# BIOGAS.net
KiCad netlist of a schematic drawn in EAGLE
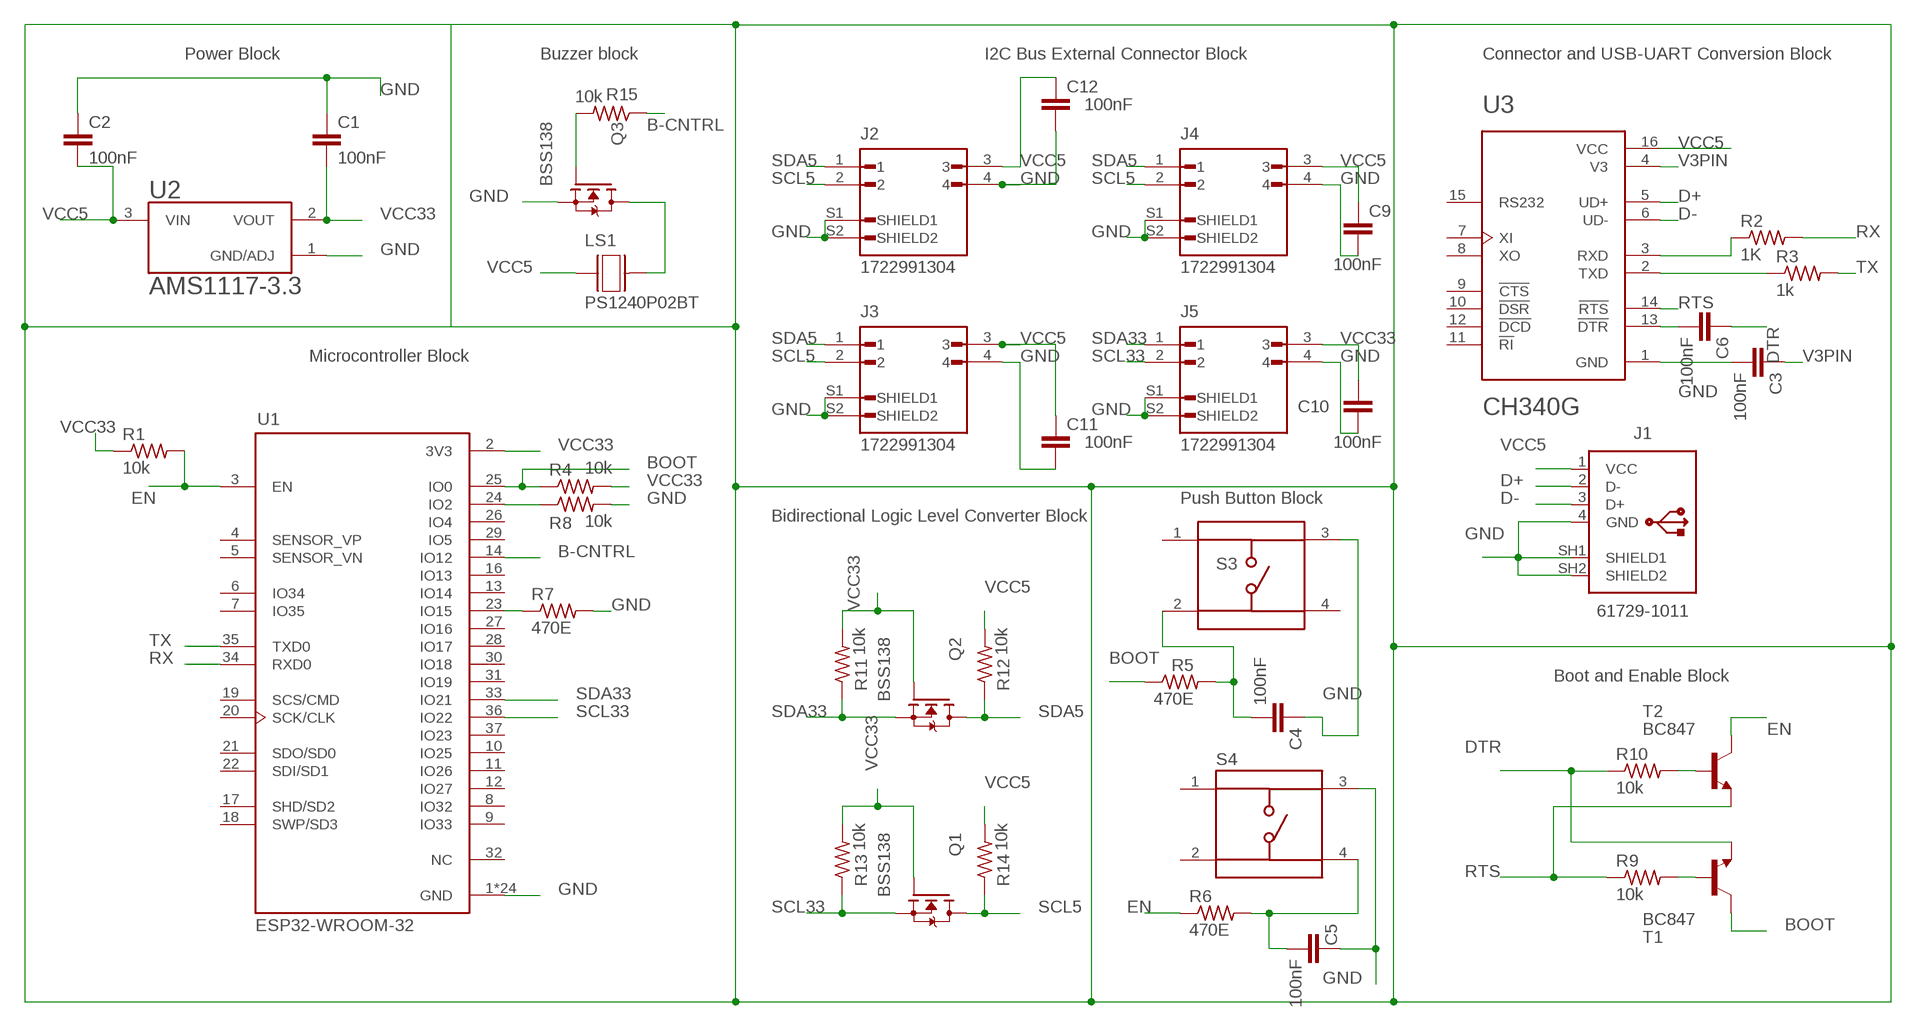
[diagram p0: schematic, sheet 1]

(export (version "E")
  (design (tool "Eeschema 10.0.6"))
  (components
    (comp (ref "C1")
      (value "100nF")
      (footprint "eagle-import:C1206")
      (libsource (lib "eagle-import") (part "CAPACITOR_SMD_1206"))
    )
    (comp (ref "C2")
      (value "100nF")
      (footprint "eagle-import:C1206")
      (libsource (lib "eagle-import") (part "CAPACITOR_SMD_1206"))
    )
    (comp (ref "C3")
      (value "100nF")
      (footprint "eagle-import:C1206")
      (libsource (lib "eagle-import") (part "CAPACITOR_SMD_1206"))
    )
    (comp (ref "C4")
      (value "100nF")
      (footprint "eagle-import:C1206")
      (libsource (lib "eagle-import") (part "CAPACITOR_SMD_1206"))
    )
    (comp (ref "C5")
      (value "100nF")
      (footprint "eagle-import:C1206")
      (libsource (lib "eagle-import") (part "CAPACITOR_SMD_1206"))
    )
    (comp (ref "C6")
      (value "100nF")
      (footprint "eagle-import:C1206")
      (libsource (lib "eagle-import") (part "CAPACITOR_SMD_1206"))
    )
    (comp (ref "C9")
      (value "100nF")
      (footprint "eagle-import:C1206")
      (libsource (lib "eagle-import") (part "CAPACITOR_SMD_1206"))
    )
    (comp (ref "C10")
      (value "100nF")
      (footprint "eagle-import:C1206")
      (libsource (lib "eagle-import") (part "CAPACITOR_SMD_1206"))
    )
    (comp (ref "C11")
      (value "100nF")
      (footprint "eagle-import:C1206")
      (libsource (lib "eagle-import") (part "CAPACITOR_SMD_1206"))
    )
    (comp (ref "C12")
      (value "100nF")
      (footprint "eagle-import:C1206")
      (libsource (lib "eagle-import") (part "CAPACITOR_SMD_1206"))
    )
    (comp (ref "J1")
      (value "61729-1011")
      (footprint "eagle-import:61729-1011BLF")
      (fields (field (name "MANUFACTURER") "Amphenol ICC (FCI)") (field (name "MPN") "61729-1011BLF"))
      (libsource (lib "eagle-import") (part "61729-1011"))
    )
    (comp (ref "J2")
      (value "1722991304")
      (footprint "eagle-import:MOLEX_1722991304")
      (fields (field (name "MANUFACTURER") "Molex"))
      (libsource (lib "eagle-import") (part "1722991304"))
    )
    (comp (ref "J3")
      (value "1722991304")
      (footprint "eagle-import:MOLEX_1722991304")
      (fields (field (name "MANUFACTURER") "Molex"))
      (libsource (lib "eagle-import") (part "1722991304"))
    )
    (comp (ref "J4")
      (value "1722991304")
      (footprint "eagle-import:MOLEX_1722991304")
      (fields (field (name "MANUFACTURER") "Molex"))
      (libsource (lib "eagle-import") (part "1722991304"))
    )
    (comp (ref "J5")
      (value "1722991304")
      (footprint "eagle-import:MOLEX_1722991304")
      (fields (field (name "MANUFACTURER") "Molex"))
      (libsource (lib "eagle-import") (part "1722991304"))
    )
    (comp (ref "LS1")
      (value "PS1240P02BT")
      (footprint "eagle-import:XDCR_PS1240P02BT")
      (fields (field (name "MF") "TDK") (field (name "MP") "PS1240P02CT3"))
      (libsource (lib "eagle-import") (part "PS1240P02BT"))
    )
    (comp (ref "Q1")
      (value "BSS138")
      (footprint "eagle-import:SOT95P240X111-3N")
      (fields (field (name "MANUFACTURER") "ON Semiconductor"))
      (libsource (lib "eagle-import") (part "BSS138"))
    )
    (comp (ref "Q2")
      (value "BSS138")
      (footprint "eagle-import:SOT95P240X111-3N")
      (fields (field (name "MANUFACTURER") "ON Semiconductor"))
      (libsource (lib "eagle-import") (part "BSS138"))
    )
    (comp (ref "Q3")
      (value "BSS138")
      (footprint "eagle-import:SOT95P240X111-3N")
      (fields (field (name "MANUFACTURER") "ON Semiconductor"))
      (libsource (lib "eagle-import") (part "BSS138"))
    )
    (comp (ref "R1")
      (value "10k")
      (footprint "eagle-import:M1206")
      (libsource (lib "eagle-import") (part "RESISTOR_SMD_1206"))
    )
    (comp (ref "R2")
      (value "1K")
      (footprint "eagle-import:M1206")
      (libsource (lib "eagle-import") (part "RESISTOR_SMD_1206"))
    )
    (comp (ref "R3")
      (value "1k")
      (footprint "eagle-import:M1206")
      (libsource (lib "eagle-import") (part "RESISTOR_SMD_1206"))
    )
    (comp (ref "R4")
      (value "10k")
      (footprint "eagle-import:M1206")
      (libsource (lib "eagle-import") (part "RESISTOR_SMD_1206"))
    )
    (comp (ref "R5")
      (value "470E")
      (footprint "eagle-import:M1206")
      (libsource (lib "eagle-import") (part "RESISTOR_SMD_1206"))
    )
    (comp (ref "R6")
      (value "470E")
      (footprint "eagle-import:M1206")
      (libsource (lib "eagle-import") (part "RESISTOR_SMD_1206"))
    )
    (comp (ref "R7")
      (value "470E")
      (footprint "eagle-import:M1206")
      (libsource (lib "eagle-import") (part "RESISTOR_SMD_1206"))
    )
    (comp (ref "R8")
      (value "10k")
      (footprint "eagle-import:M1206")
      (libsource (lib "eagle-import") (part "RESISTOR_SMD_1206"))
    )
    (comp (ref "R9")
      (value "10k")
      (footprint "eagle-import:M1206")
      (libsource (lib "eagle-import") (part "RESISTOR_SMD_1206"))
    )
    (comp (ref "R10")
      (value "10k")
      (footprint "eagle-import:M1206")
      (libsource (lib "eagle-import") (part "RESISTOR_SMD_1206"))
    )
    (comp (ref "R11")
      (value "10k")
      (footprint "eagle-import:M1206")
      (libsource (lib "eagle-import") (part "RESISTOR_SMD_1206"))
    )
    (comp (ref "R12")
      (value "10k")
      (footprint "eagle-import:M1206")
      (libsource (lib "eagle-import") (part "RESISTOR_SMD_1206"))
    )
    (comp (ref "R13")
      (value "10k")
      (footprint "eagle-import:M1206")
      (libsource (lib "eagle-import") (part "RESISTOR_SMD_1206"))
    )
    (comp (ref "R14")
      (value "10k")
      (footprint "eagle-import:M1206")
      (libsource (lib "eagle-import") (part "RESISTOR_SMD_1206"))
    )
    (comp (ref "R15")
      (value "10k")
      (footprint "eagle-import:M1206")
      (libsource (lib "eagle-import") (part "RESISTOR_SMD_1206"))
    )
    (comp (ref "S3")
      (value "TS04-66-55-BK-260-SMT")
      (footprint "eagle-import:SW_TS04-66-55-BK-260-SMT")
      (fields (field (name "MANUFACTURER") "CUI Devices"))
      (libsource (lib "eagle-import") (part "TS04-66-55-BK-260-SMT"))
    )
    (comp (ref "S4")
      (value "TS04-66-55-BK-260-SMT")
      (footprint "eagle-import:SW_TS04-66-55-BK-260-SMT")
      (fields (field (name "MANUFACTURER") "CUI Devices"))
      (libsource (lib "eagle-import") (part "TS04-66-55-BK-260-SMT"))
    )
    (comp (ref "T1")
      (value "BC847")
      (footprint "eagle-import:SOT23")
      (libsource (lib "eagle-import") (part "BC847"))
    )
    (comp (ref "T2")
      (value "BC847")
      (footprint "eagle-import:SOT23")
      (libsource (lib "eagle-import") (part "BC847"))
    )
    (comp (ref "U1")
      (value "ESP32-WROOM-32")
      (footprint "eagle-import:MODULE_ESP32-WROOM-32")
      (fields (field (name "MANUFACTURER") "Espressif Systems"))
      (libsource (lib "eagle-import") (part "ESP32-WROOM-32"))
    )
    (comp (ref "U2")
      (value "AMS1117-3.3")
      (footprint "eagle-import:SOT229P700X180-4N")
      (fields (field (name "MANUFACTURER") "Advanced Monolithic Systems"))
      (libsource (lib "eagle-import") (part "AMS1117-3.3"))
    )
    (comp (ref "U3")
      (value "CH340G")
      (footprint "eagle-import:SOIC127P600X180-16N")
      (fields (field (name "MANUFACTURER") "WCH"))
      (libsource (lib "eagle-import") (part "CH340G"))
    )
  )
  (nets
    (net (code "1") (name "/B-CNTRL") (class "Default")
      (node (ref "R15") (pin "1") (pinfunction "1_1") (pintype "passive"))
      (node (ref "U1") (pin "14") (pinfunction "IO12_14") (pintype "bidirectional"))
    )
    (net (code "2") (name "/BOOT") (class "Default")
      (node (ref "R4") (pin "1") (pinfunction "1_1") (pintype "passive"))
      (node (ref "R5") (pin "1") (pinfunction "1_1") (pintype "passive"))
      (node (ref "T1") (pin "3") (pinfunction "C_3") (pintype "passive"))
      (node (ref "U1") (pin "25") (pinfunction "IO0_25") (pintype "bidirectional"))
    )
    (net (code "3") (name "/D+") (class "Default")
      (node (ref "J1") (pin "2") (pinfunction "D-_2") (pintype "bidirectional"))
      (node (ref "U3") (pin "5") (pinfunction "UD+_5") (pintype "bidirectional"))
    )
    (net (code "4") (name "/D-") (class "Default")
      (node (ref "J1") (pin "3") (pinfunction "D+_3") (pintype "bidirectional"))
      (node (ref "U3") (pin "6") (pinfunction "UD-_6") (pintype "bidirectional"))
    )
    (net (code "5") (name "/DTR") (class "Default")
      (node (ref "C6") (pin "1") (pinfunction "1_1") (pintype "passive"))
      (node (ref "R10") (pin "1") (pinfunction "1_1") (pintype "passive"))
      (node (ref "T1") (pin "2") (pinfunction "E_2") (pintype "passive"))
    )
    (net (code "6") (name "/EN") (class "Default")
      (node (ref "R1") (pin "2") (pinfunction "2_2") (pintype "passive"))
      (node (ref "R6") (pin "1") (pinfunction "1_1") (pintype "passive"))
      (node (ref "T2") (pin "3") (pinfunction "C_3") (pintype "passive"))
      (node (ref "U1") (pin "3") (pinfunction "EN_3") (pintype "input"))
    )
    (net (code "7") (name "/GND") (class "Default")
      (node (ref "C1") (pin "1") (pinfunction "1_1") (pintype "passive"))
      (node (ref "C10") (pin "2") (pinfunction "2_2") (pintype "passive"))
      (node (ref "C11") (pin "2") (pinfunction "2_2") (pintype "passive"))
      (node (ref "C12") (pin "2") (pinfunction "2_2") (pintype "passive"))
      (node (ref "C2") (pin "1") (pinfunction "1_1") (pintype "passive"))
      (node (ref "C3") (pin "2") (pinfunction "2_2") (pintype "passive"))
      (node (ref "C4") (pin "1") (pinfunction "1_1") (pintype "passive"))
      (node (ref "C5") (pin "1") (pinfunction "1_1") (pintype "passive"))
      (node (ref "C9") (pin "2") (pinfunction "2_2") (pintype "passive"))
      (node (ref "J1") (pin "4") (pinfunction "GND_4") (pintype "power_in"))
      (node (ref "J1") (pin "SH1") (pinfunction "SHIELD1_SH1") (pintype "power_in"))
      (node (ref "J1") (pin "SH2") (pinfunction "SHIELD2_SH2") (pintype "power_in"))
      (node (ref "J2") (pin "4") (pinfunction "4_4") (pintype "passive"))
      (node (ref "J2") (pin "S1") (pinfunction "SHIELD1_S1") (pintype "passive"))
      (node (ref "J2") (pin "S2") (pinfunction "SHIELD2_S2") (pintype "passive"))
      (node (ref "J3") (pin "4") (pinfunction "4_4") (pintype "passive"))
      (node (ref "J3") (pin "S1") (pinfunction "SHIELD1_S1") (pintype "passive"))
      (node (ref "J3") (pin "S2") (pinfunction "SHIELD2_S2") (pintype "passive"))
      (node (ref "J4") (pin "4") (pinfunction "4_4") (pintype "passive"))
      (node (ref "J4") (pin "S1") (pinfunction "SHIELD1_S1") (pintype "passive"))
      (node (ref "J4") (pin "S2") (pinfunction "SHIELD2_S2") (pintype "passive"))
      (node (ref "J5") (pin "4") (pinfunction "4_4") (pintype "passive"))
      (node (ref "J5") (pin "S1") (pinfunction "SHIELD1_S1") (pintype "passive"))
      (node (ref "J5") (pin "S2") (pinfunction "SHIELD2_S2") (pintype "passive"))
      (node (ref "Q3") (pin "2") (pinfunction "S_2") (pintype "passive"))
      (node (ref "R7") (pin "2") (pinfunction "2_2") (pintype "passive"))
      (node (ref "R8") (pin "2") (pinfunction "2_2") (pintype "passive"))
      (node (ref "S3") (pin "3") (pinfunction "3_3") (pintype "passive"))
      (node (ref "S4") (pin "3") (pinfunction "3_3") (pintype "passive"))
      (node (ref "U1") (pin "1") (pinfunction "GND_1") (pintype "power_in"))
      (node (ref "U1") (pin "15") (pinfunction "GND_15") (pintype "power_in"))
      (node (ref "U1") (pin "38") (pinfunction "GND_38") (pintype "power_in"))
      (node (ref "U1") (pin "39_1") (pinfunction "GND_39_1") (pintype "power_in"))
      (node (ref "U1") (pin "39_10") (pinfunction "GND_39_10") (pintype "power_in"))
      (node (ref "U1") (pin "39_11") (pinfunction "GND_39_11") (pintype "power_in"))
      (node (ref "U1") (pin "39_12") (pinfunction "GND_39_12") (pintype "power_in"))
      (node (ref "U1") (pin "39_13") (pinfunction "GND_39_13") (pintype "power_in"))
      (node (ref "U1") (pin "39_14") (pinfunction "GND_39_14") (pintype "power_in"))
      (node (ref "U1") (pin "39_15") (pinfunction "GND_39_15") (pintype "power_in"))
      (node (ref "U1") (pin "39_16") (pinfunction "GND_39_16") (pintype "power_in"))
      (node (ref "U1") (pin "39_17") (pinfunction "GND_39_17") (pintype "power_in"))
      (node (ref "U1") (pin "39_18") (pinfunction "GND_39_18") (pintype "power_in"))
      (node (ref "U1") (pin "39_19") (pinfunction "GND_39_19") (pintype "power_in"))
      (node (ref "U1") (pin "39_2") (pinfunction "GND_39_2") (pintype "power_in"))
      (node (ref "U1") (pin "39_20") (pinfunction "GND_39_20") (pintype "power_in"))
      (node (ref "U1") (pin "39_21") (pinfunction "GND_39_21") (pintype "power_in"))
      (node (ref "U1") (pin "39_3") (pinfunction "GND_39_3") (pintype "power_in"))
      (node (ref "U1") (pin "39_4") (pinfunction "GND_39_4") (pintype "power_in"))
      (node (ref "U1") (pin "39_5") (pinfunction "GND_39_5") (pintype "power_in"))
      (node (ref "U1") (pin "39_6") (pinfunction "GND_39_6") (pintype "power_in"))
      (node (ref "U1") (pin "39_7") (pinfunction "GND_39_7") (pintype "power_in"))
      (node (ref "U1") (pin "39_8") (pinfunction "GND_39_8") (pintype "power_in"))
      (node (ref "U1") (pin "39_9") (pinfunction "GND_39_9") (pintype "power_in"))
      (node (ref "U2") (pin "1") (pinfunction "GND/ADJ_1") (pintype "power_in"))
      (node (ref "U3") (pin "1") (pinfunction "GND_1") (pintype "power_in"))
    )
    (net (code "8") (name "/RTS") (class "Default")
      (node (ref "R9") (pin "1") (pinfunction "1_1") (pintype "passive"))
      (node (ref "T2") (pin "2") (pinfunction "E_2") (pintype "passive"))
      (node (ref "U3") (pin "14") (pinfunction "~{RTS}_14") (pintype "output"))
    )
    (net (code "9") (name "/RX") (class "Default")
      (node (ref "R2") (pin "2") (pinfunction "2_2") (pintype "passive"))
      (node (ref "U1") (pin "34") (pinfunction "RXD0_34") (pintype "bidirectional"))
    )
    (net (code "10") (name "/SCL5") (class "Default")
      (node (ref "J2") (pin "2") (pinfunction "2_2") (pintype "passive"))
      (node (ref "J3") (pin "2") (pinfunction "2_2") (pintype "passive"))
      (node (ref "J4") (pin "2") (pinfunction "2_2") (pintype "passive"))
      (node (ref "Q1") (pin "3") (pinfunction "D_3") (pintype "passive"))
      (node (ref "R14") (pin "1") (pinfunction "1_1") (pintype "passive"))
    )
    (net (code "11") (name "/SCL33") (class "Default")
      (node (ref "J5") (pin "2") (pinfunction "2_2") (pintype "passive"))
      (node (ref "Q1") (pin "2") (pinfunction "S_2") (pintype "passive"))
      (node (ref "R13") (pin "1") (pinfunction "1_1") (pintype "passive"))
      (node (ref "U1") (pin "36") (pinfunction "IO22_36") (pintype "bidirectional"))
    )
    (net (code "12") (name "/SDA5") (class "Default")
      (node (ref "J2") (pin "1") (pinfunction "1_1") (pintype "passive"))
      (node (ref "J3") (pin "1") (pinfunction "1_1") (pintype "passive"))
      (node (ref "J4") (pin "1") (pinfunction "1_1") (pintype "passive"))
      (node (ref "Q2") (pin "3") (pinfunction "D_3") (pintype "passive"))
      (node (ref "R12") (pin "1") (pinfunction "1_1") (pintype "passive"))
    )
    (net (code "13") (name "/SDA33") (class "Default")
      (node (ref "J5") (pin "1") (pinfunction "1_1") (pintype "passive"))
      (node (ref "Q2") (pin "2") (pinfunction "S_2") (pintype "passive"))
      (node (ref "R11") (pin "1") (pinfunction "1_1") (pintype "passive"))
      (node (ref "U1") (pin "33") (pinfunction "IO21_33") (pintype "bidirectional"))
    )
    (net (code "14") (name "/TX") (class "Default")
      (node (ref "R3") (pin "2") (pinfunction "2_2") (pintype "passive"))
      (node (ref "U1") (pin "35") (pinfunction "TXD0_35") (pintype "bidirectional"))
    )
    (net (code "15") (name "/V3PIN") (class "Default")
      (node (ref "C3") (pin "1") (pinfunction "1_1") (pintype "passive"))
      (node (ref "U3") (pin "4") (pinfunction "V3_4") (pintype "power_in"))
    )
    (net (code "16") (name "/VCC5") (class "Default")
      (node (ref "C11") (pin "1") (pinfunction "1_1") (pintype "passive"))
      (node (ref "C12") (pin "1") (pinfunction "1_1") (pintype "passive"))
      (node (ref "C2") (pin "2") (pinfunction "2_2") (pintype "passive"))
      (node (ref "C9") (pin "1") (pinfunction "1_1") (pintype "passive"))
      (node (ref "J1") (pin "1") (pinfunction "VCC_1") (pintype "power_in"))
      (node (ref "J2") (pin "3") (pinfunction "3_3") (pintype "passive"))
      (node (ref "J3") (pin "3") (pinfunction "3_3") (pintype "passive"))
      (node (ref "J4") (pin "3") (pinfunction "3_3") (pintype "passive"))
      (node (ref "LS1") (pin "1") (pinfunction "1_1") (pintype "passive"))
      (node (ref "R12") (pin "2") (pinfunction "2_2") (pintype "passive"))
      (node (ref "R14") (pin "2") (pinfunction "2_2") (pintype "passive"))
      (node (ref "U2") (pin "3") (pinfunction "VIN_3") (pintype "input"))
      (node (ref "U3") (pin "16") (pinfunction "VCC_16") (pintype "power_in"))
    )
    (net (code "17") (name "/VCC33") (class "Default")
      (node (ref "C1") (pin "2") (pinfunction "2_2") (pintype "passive"))
      (node (ref "C10") (pin "1") (pinfunction "1_1") (pintype "passive"))
      (node (ref "J5") (pin "3") (pinfunction "3_3") (pintype "passive"))
      (node (ref "Q1") (pin "1") (pinfunction "G_1") (pintype "passive"))
      (node (ref "Q2") (pin "1") (pinfunction "G_1") (pintype "passive"))
      (node (ref "R1") (pin "1") (pinfunction "1_1") (pintype "passive"))
      (node (ref "R11") (pin "2") (pinfunction "2_2") (pintype "passive"))
      (node (ref "R13") (pin "2") (pinfunction "2_2") (pintype "passive"))
      (node (ref "R4") (pin "2") (pinfunction "2_2") (pintype "passive"))
      (node (ref "U1") (pin "2") (pinfunction "3V3_2") (pintype "power_in"))
      (node (ref "U2") (pin "2") (pinfunction "VOUT_2") (pintype "output"))
    )
    (net (code "18") (name "Net-(C4-Pad2)") (class "Default")
      (node (ref "C4") (pin "2") (pinfunction "2_2") (pintype "passive"))
      (node (ref "R5") (pin "2") (pinfunction "2_2") (pintype "passive"))
      (node (ref "S3") (pin "2") (pinfunction "2_2") (pintype "passive"))
    )
    (net (code "19") (name "Net-(C5-Pad2)") (class "Default")
      (node (ref "C5") (pin "2") (pinfunction "2_2") (pintype "passive"))
      (node (ref "R6") (pin "2") (pinfunction "2_2") (pintype "passive"))
      (node (ref "S4") (pin "4") (pinfunction "4_4") (pintype "passive"))
    )
    (net (code "20") (name "Net-(Q3-D)") (class "Default")
      (node (ref "LS1") (pin "2") (pinfunction "2_2") (pintype "passive"))
      (node (ref "Q3") (pin "3") (pinfunction "D_3") (pintype "passive"))
    )
    (net (code "21") (name "Net-(Q3-G)") (class "Default")
      (node (ref "Q3") (pin "1") (pinfunction "G_1") (pintype "passive"))
      (node (ref "R15") (pin "2") (pinfunction "2_2") (pintype "passive"))
    )
    (net (code "22") (name "Net-(T1-B)") (class "Default")
      (node (ref "R9") (pin "2") (pinfunction "2_2") (pintype "passive"))
      (node (ref "T1") (pin "1") (pinfunction "B_1") (pintype "passive"))
    )
    (net (code "23") (name "Net-(T2-B)") (class "Default")
      (node (ref "R10") (pin "2") (pinfunction "2_2") (pintype "passive"))
      (node (ref "T2") (pin "1") (pinfunction "B_1") (pintype "passive"))
    )
    (net (code "24") (name "Net-(U1-IO2)") (class "Default")
      (node (ref "R8") (pin "1") (pinfunction "1_1") (pintype "passive"))
      (node (ref "U1") (pin "24") (pinfunction "IO2_24") (pintype "bidirectional"))
    )
    (net (code "25") (name "Net-(U1-IO15)") (class "Default")
      (node (ref "R7") (pin "1") (pinfunction "1_1") (pintype "passive"))
      (node (ref "U1") (pin "23") (pinfunction "IO15_23") (pintype "bidirectional"))
    )
    (net (code "26") (name "Net-(U3-RXD)") (class "Default")
      (node (ref "R2") (pin "1") (pinfunction "1_1") (pintype "passive"))
      (node (ref "U3") (pin "3") (pinfunction "RXD_3") (pintype "input"))
    )
    (net (code "27") (name "Net-(U3-TXD)") (class "Default")
      (node (ref "R3") (pin "1") (pinfunction "1_1") (pintype "passive"))
      (node (ref "U3") (pin "2") (pinfunction "TXD_2") (pintype "output"))
    )
    (net (code "28") (name "Net-(U3-~{DTR})") (class "Default")
      (node (ref "C6") (pin "2") (pinfunction "2_2") (pintype "passive"))
      (node (ref "U3") (pin "13") (pinfunction "~{DTR}_13") (pintype "output"))
    )
    (net (code "29") (name "unconnected-(S3-Pad1)") (class "Default")
      (node (ref "S3") (pin "1") (pinfunction "1_1") (pintype "passive"))
    )
    (net (code "30") (name "unconnected-(S3-Pad4)") (class "Default")
      (node (ref "S3") (pin "4") (pinfunction "4_4") (pintype "passive"))
    )
    (net (code "31") (name "unconnected-(S4-Pad1)") (class "Default")
      (node (ref "S4") (pin "1") (pinfunction "1_1") (pintype "passive"))
    )
    (net (code "32") (name "unconnected-(S4-Pad2)") (class "Default")
      (node (ref "S4") (pin "2") (pinfunction "2_2") (pintype "passive"))
    )
    (net (code "33") (name "unconnected-(U1-IO4-Pad26)") (class "Default")
      (node (ref "U1") (pin "26") (pinfunction "IO4_26") (pintype "bidirectional"))
    )
    (net (code "34") (name "unconnected-(U1-IO5-Pad29)") (class "Default")
      (node (ref "U1") (pin "29") (pinfunction "IO5_29") (pintype "bidirectional"))
    )
    (net (code "35") (name "unconnected-(U1-IO13-Pad16)") (class "Default")
      (node (ref "U1") (pin "16") (pinfunction "IO13_16") (pintype "bidirectional"))
    )
    (net (code "36") (name "unconnected-(U1-IO14-Pad13)") (class "Default")
      (node (ref "U1") (pin "13") (pinfunction "IO14_13") (pintype "bidirectional"))
    )
    (net (code "37") (name "unconnected-(U1-IO16-Pad27)") (class "Default")
      (node (ref "U1") (pin "27") (pinfunction "IO16_27") (pintype "bidirectional"))
    )
    (net (code "38") (name "unconnected-(U1-IO17-Pad28)") (class "Default")
      (node (ref "U1") (pin "28") (pinfunction "IO17_28") (pintype "bidirectional"))
    )
    (net (code "39") (name "unconnected-(U1-IO18-Pad30)") (class "Default")
      (node (ref "U1") (pin "30") (pinfunction "IO18_30") (pintype "bidirectional"))
    )
    (net (code "40") (name "unconnected-(U1-IO19-Pad31)") (class "Default")
      (node (ref "U1") (pin "31") (pinfunction "IO19_31") (pintype "bidirectional"))
    )
    (net (code "41") (name "unconnected-(U1-IO23-Pad37)") (class "Default")
      (node (ref "U1") (pin "37") (pinfunction "IO23_37") (pintype "bidirectional"))
    )
    (net (code "42") (name "unconnected-(U1-IO25-Pad10)") (class "Default")
      (node (ref "U1") (pin "10") (pinfunction "IO25_10") (pintype "bidirectional"))
    )
    (net (code "43") (name "unconnected-(U1-IO26-Pad11)") (class "Default")
      (node (ref "U1") (pin "11") (pinfunction "IO26_11") (pintype "bidirectional"))
    )
    (net (code "44") (name "unconnected-(U1-IO27-Pad12)") (class "Default")
      (node (ref "U1") (pin "12") (pinfunction "IO27_12") (pintype "bidirectional"))
    )
    (net (code "45") (name "unconnected-(U1-IO32-Pad8)") (class "Default")
      (node (ref "U1") (pin "8") (pinfunction "IO32_8") (pintype "bidirectional"))
    )
    (net (code "46") (name "unconnected-(U1-IO33-Pad9)") (class "Default")
      (node (ref "U1") (pin "9") (pinfunction "IO33_9") (pintype "bidirectional"))
    )
    (net (code "47") (name "unconnected-(U1-IO34-Pad6)") (class "Default")
      (node (ref "U1") (pin "6") (pinfunction "IO34_6") (pintype "input"))
    )
    (net (code "48") (name "unconnected-(U1-IO35-Pad7)") (class "Default")
      (node (ref "U1") (pin "7") (pinfunction "IO35_7") (pintype "input"))
    )
    (net (code "49") (name "unconnected-(U1-NC-Pad32)") (class "Default")
      (node (ref "U1") (pin "32") (pinfunction "NC_32") (pintype "no_connect"))
    )
    (net (code "50") (name "unconnected-(U1-SCK{slash}CLK-Pad20)") (class "Default")
      (node (ref "U1") (pin "20") (pinfunction "SCK/CLK_20") (pintype "bidirectional"))
    )
    (net (code "51") (name "unconnected-(U1-SCS{slash}CMD-Pad19)") (class "Default")
      (node (ref "U1") (pin "19") (pinfunction "SCS/CMD_19") (pintype "bidirectional"))
    )
    (net (code "52") (name "unconnected-(U1-SDI{slash}SD1-Pad22)") (class "Default")
      (node (ref "U1") (pin "22") (pinfunction "SDI/SD1_22") (pintype "bidirectional"))
    )
    (net (code "53") (name "unconnected-(U1-SDO{slash}SD0-Pad21)") (class "Default")
      (node (ref "U1") (pin "21") (pinfunction "SDO/SD0_21") (pintype "bidirectional"))
    )
    (net (code "54") (name "unconnected-(U1-SENSOR_VN-Pad5)") (class "Default")
      (node (ref "U1") (pin "5") (pinfunction "SENSOR_VN_5") (pintype "input"))
    )
    (net (code "55") (name "unconnected-(U1-SENSOR_VP-Pad4)") (class "Default")
      (node (ref "U1") (pin "4") (pinfunction "SENSOR_VP_4") (pintype "input"))
    )
    (net (code "56") (name "unconnected-(U1-SHD{slash}SD2-Pad17)") (class "Default")
      (node (ref "U1") (pin "17") (pinfunction "SHD/SD2_17") (pintype "bidirectional"))
    )
    (net (code "57") (name "unconnected-(U1-SWP{slash}SD3-Pad18)") (class "Default")
      (node (ref "U1") (pin "18") (pinfunction "SWP/SD3_18") (pintype "bidirectional"))
    )
    (net (code "58") (name "unconnected-(U3-RS232-Pad15)") (class "Default")
      (node (ref "U3") (pin "15") (pinfunction "RS232_15") (pintype "input"))
    )
    (net (code "59") (name "unconnected-(U3-XI-Pad7)") (class "Default")
      (node (ref "U3") (pin "7") (pinfunction "XI_7") (pintype "input"))
    )
    (net (code "60") (name "unconnected-(U3-XO-Pad8)") (class "Default")
      (node (ref "U3") (pin "8") (pinfunction "XO_8") (pintype "output"))
    )
    (net (code "61") (name "unconnected-(U3-~{CTS}-Pad9)") (class "Default")
      (node (ref "U3") (pin "9") (pinfunction "~{CTS}_9") (pintype "input"))
    )
    (net (code "62") (name "unconnected-(U3-~{DCD}-Pad12)") (class "Default")
      (node (ref "U3") (pin "12") (pinfunction "~{DCD}_12") (pintype "input"))
    )
    (net (code "63") (name "unconnected-(U3-~{DSR}-Pad10)") (class "Default")
      (node (ref "U3") (pin "10") (pinfunction "~{DSR}_10") (pintype "input"))
    )
    (net (code "64") (name "unconnected-(U3-~{RI}-Pad11)") (class "Default")
      (node (ref "U3") (pin "11") (pinfunction "~{RI}_11") (pintype "input"))
    )
  )
)
